# BMI088_I2C_Breakout_V1_0_Schematic.net
KiCad netlist of a schematic drawn in Altium Designer
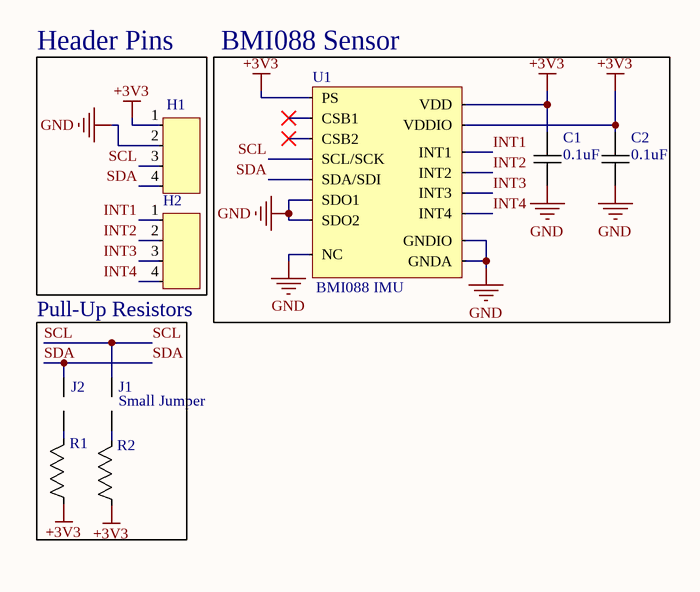
[diagram p0: BMI088 I2C Breakout V1.0 Schematic.SchDoc]

(export (version "E")
  (design (tool "Eeschema 10.0.6"))
  (components
    (comp (ref "C1")
      (value "0.1uF")
      (footprint "CL10B104KB8NNWC 0.1uF 0603-Footprint-1")
      (description "CL10B104KB8NNWC 0.1uF 0603 +-10% SMD")
      (libsource (lib "University of Colorado Boulder") (part "CL10B104KB8NNWC 0.1uF 0603-Symbol-1"))
    )
    (comp (ref "C2")
      (value "0.1uF")
      (footprint "CL10B104KB8NNWC 0.1uF 0603-Footprint-1")
      (description "CL10B104KB8NNWC 0.1uF 0603 +-10% SMD")
      (libsource (lib "University of Colorado Boulder") (part "CL10B104KB8NNWC 0.1uF 0603-Symbol-1"))
    )
    (comp (ref "H1")
      (value "PR20204VBNN 4 Pin Male Header Pin 2.54mm")
      (footprint "PR20204VBNN 4 Pin Male Header Pin 2.54mm-Footprint-1")
      (description "PR20204VBNN 4 Pin Male Header Pin 2.54mm General Use")
      (libsource (lib "University of Colorado Boulder") (part "Header Pin"))
    )
    (comp (ref "H2")
      (value "PR20204VBNN 4 Pin Male Header Pin 2.54mm")
      (footprint "PR20204VBNN 4 Pin Male Header Pin 2.54mm-Footprint-1")
      (description "PR20204VBNN 4 Pin Male Header Pin 2.54mm General Use")
      (libsource (lib "University of Colorado Boulder") (part "Header Pin"))
    )
    (comp (ref "J1")
      (value "Small Jumper")
      (footprint "Small Jumper-Footprint-1")
      (description "Small Jumper For Low Current And Voltage")
      (libsource (lib "University of Colorado Boulder") (part "Component_1"))
    )
    (comp (ref "J2")
      (value "Small Jumper")
      (footprint "Small Jumper-Footprint-1")
      (description "Small Jumper For Low Current And Voltage")
      (libsource (lib "University of Colorado Boulder") (part "Component_1"))
    )
    (comp (ref "R1")
      (value "WR06X152 JTL 1.5K Ohm 0603")
      (footprint "WR06X152 JTL 1.5K Ohm 0603-Footprint-1")
      (description "WR06X152 JTL 1.5K Ohm 0603 +-5% SMD")
      (libsource (lib "University of Colorado Boulder") (part "WR06X152 JTL 1.5K Ohm 0603-Symbol-1"))
    )
    (comp (ref "R2")
      (value "WR06X152 JTL 1.5K Ohm 0603")
      (footprint "WR06X152 JTL 1.5K Ohm 0603-Footprint-1")
      (description "WR06X152 JTL 1.5K Ohm 0603 +-5% SMD")
      (libsource (lib "University of Colorado Boulder") (part "WR06X152 JTL 1.5K Ohm 0603-Symbol-1"))
    )
    (comp (ref "U1")
      (value "BMI088 IMU")
      (footprint "BMI088 IMU-Footprint-1")
      (description "BMI088 IMU General Use")
      (libsource (lib "University of Colorado Boulder") (part "BMI088 IMU-Symbol-1"))
    )
  )
  (nets
    (net (code "1") (name "+3V3") (class "Default")
      (node (ref "C1") (pin "2") (pinfunction "2_2") (pintype "passive"))
      (node (ref "C2") (pin "2") (pinfunction "2_2") (pintype "passive"))
      (node (ref "H1") (pin "1") (pinfunction "X_1") (pintype "power_in"))
      (node (ref "R1") (pin "1") (pinfunction "1_1") (pintype "passive"))
      (node (ref "R2") (pin "1") (pinfunction "1_1") (pintype "passive"))
      (node (ref "U1") (pin "11") (pinfunction "VDDIO_11") (pintype "power_in"))
      (node (ref "U1") (pin "3") (pinfunction "VDD_3") (pintype "power_in"))
      (node (ref "U1") (pin "7") (pinfunction "PS_7") (pintype "bidirectional"))
    )
    (net (code "2") (name "/INT1") (class "Default")
      (node (ref "H2") (pin "1") (pinfunction "X_1") (pintype "power_in"))
      (node (ref "U1") (pin "16") (pinfunction "INT1_16") (pintype "bidirectional"))
    )
    (net (code "3") (name "/INT2") (class "Default")
      (node (ref "H2") (pin "2") (pinfunction "X_2") (pintype "power_in"))
      (node (ref "U1") (pin "1") (pinfunction "INT2_1") (pintype "bidirectional"))
    )
    (net (code "4") (name "/INT3") (class "Default")
      (node (ref "H2") (pin "3") (pinfunction "X_3") (pintype "power_in"))
      (node (ref "U1") (pin "12") (pinfunction "INT3_12") (pintype "bidirectional"))
    )
    (net (code "5") (name "/INT4") (class "Default")
      (node (ref "H2") (pin "4") (pinfunction "X_4") (pintype "power_in"))
      (node (ref "U1") (pin "13") (pinfunction "INT4_13") (pintype "bidirectional"))
    )
    (net (code "6") (name "/SCL") (class "Default")
      (node (ref "H1") (pin "3") (pinfunction "X_3") (pintype "power_in"))
      (node (ref "J1") (pin "1") (pinfunction "1_1") (pintype "passive"))
      (node (ref "U1") (pin "8") (pinfunction "SCL/SCK_8") (pintype "bidirectional"))
    )
    (net (code "7") (name "/SDA") (class "Default")
      (node (ref "H1") (pin "4") (pinfunction "X_4") (pintype "power_in"))
      (node (ref "J2") (pin "1") (pinfunction "1_1") (pintype "passive"))
      (node (ref "U1") (pin "9") (pinfunction "SDA/SDI_9") (pintype "bidirectional"))
    )
    (net (code "8") (name "GND") (class "Default")
      (node (ref "C1") (pin "1") (pinfunction "1_1") (pintype "passive"))
      (node (ref "C2") (pin "1") (pinfunction "1_1") (pintype "passive"))
      (node (ref "H1") (pin "2") (pinfunction "X_2") (pintype "power_in"))
      (node (ref "U1") (pin "10") (pinfunction "SDO2_10") (pintype "bidirectional"))
      (node (ref "U1") (pin "15") (pinfunction "SDO1_15") (pintype "bidirectional"))
      (node (ref "U1") (pin "2") (pinfunction "NC_2") (pintype "power_in"))
      (node (ref "U1") (pin "4") (pinfunction "GNDA_4") (pintype "power_in"))
      (node (ref "U1") (pin "6") (pinfunction "GNDIO_6") (pintype "power_in"))
    )
    (net (code "9") (name "Net-(J1-Pad2)") (class "Default")
      (node (ref "J1") (pin "2") (pinfunction "2_2") (pintype "passive"))
      (node (ref "R2") (pin "2") (pinfunction "2_2") (pintype "passive"))
    )
    (net (code "10") (name "Net-(J2-Pad2)") (class "Default")
      (node (ref "J2") (pin "2") (pinfunction "2_2") (pintype "passive"))
      (node (ref "R1") (pin "2") (pinfunction "2_2") (pintype "passive"))
    )
    (net (code "11") (name "unconnected-(U1-CSB1-Pad14)") (class "Default")
      (node (ref "U1") (pin "14") (pinfunction "CSB1_14") (pintype "bidirectional+no_connect"))
    )
    (net (code "12") (name "unconnected-(U1-CSB2-Pad5)") (class "Default")
      (node (ref "U1") (pin "5") (pinfunction "CSB2_5") (pintype "bidirectional+no_connect"))
    )
  )
)
